# SCH_blinker_2025-11-02.net
KiCad netlist of a schematic drawn in EasyEDA
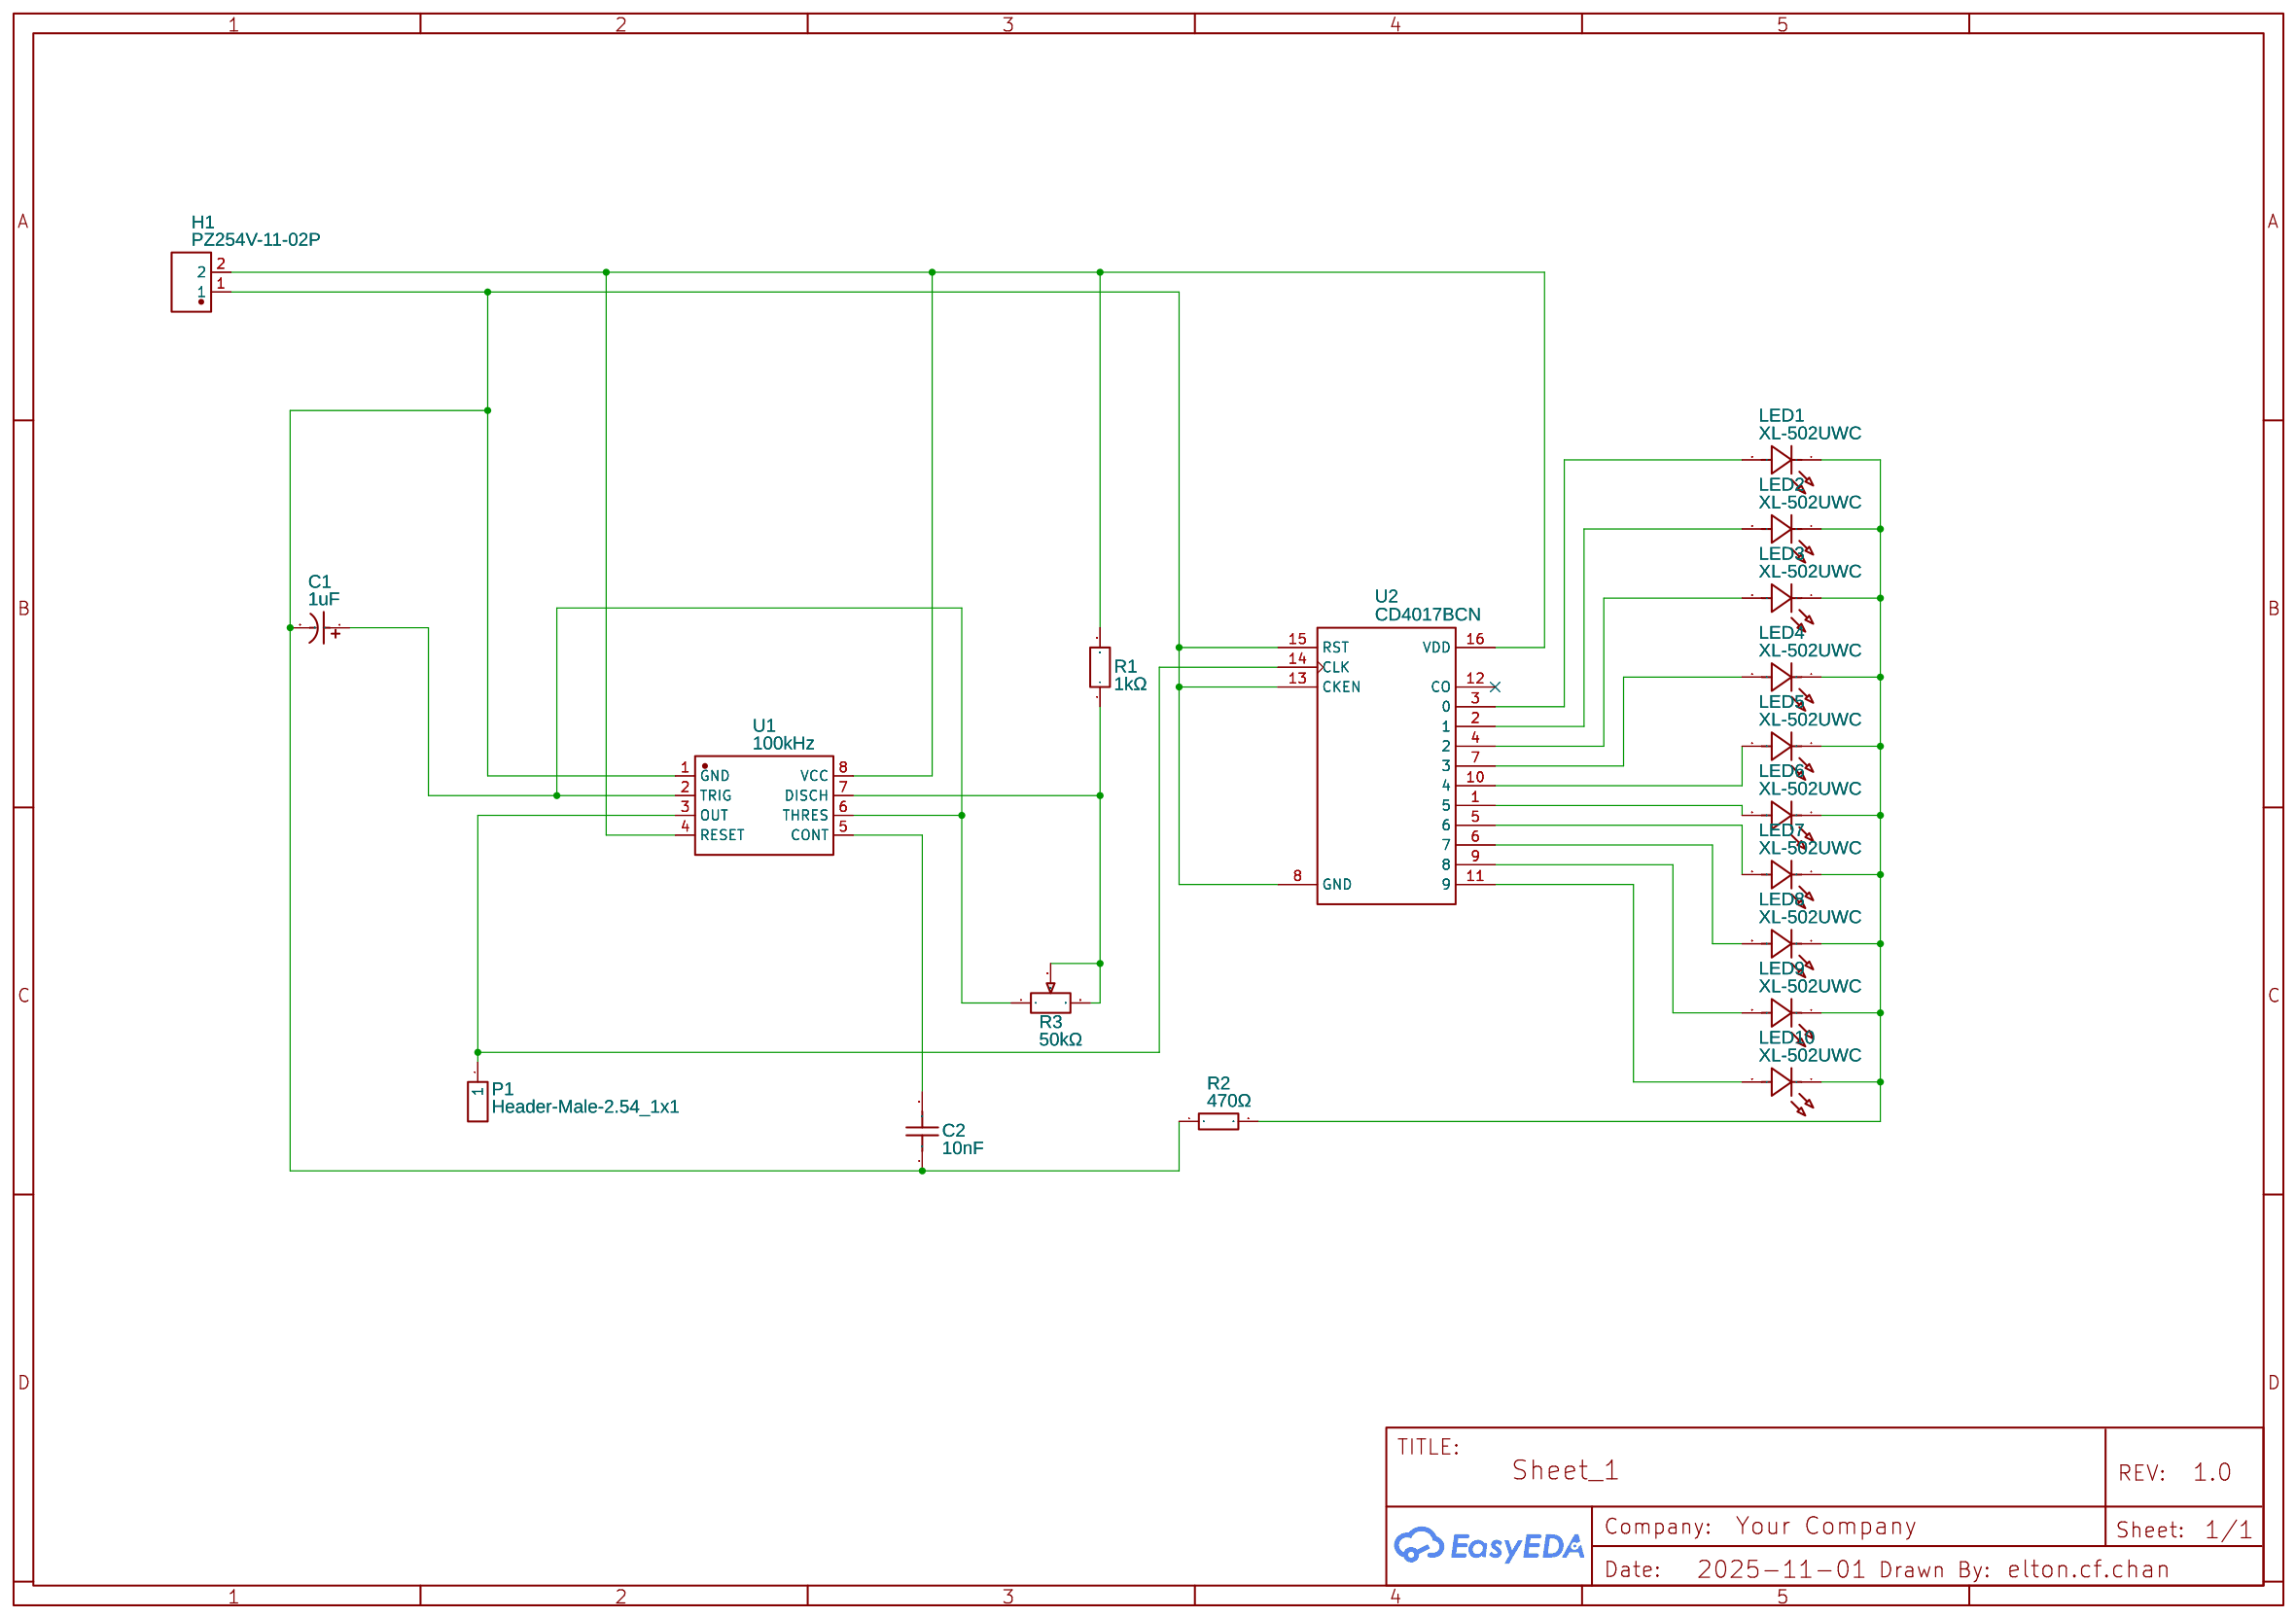
[diagram p0: schematic sheet]

(export (version "E")
  (design (tool "Eeschema 10.0.6"))
  (components
    (comp (ref "C1")
      (value "1uF")
      (fields (field (name "Manufacturer Part") "KF010M050C110A") (field (name "Manufacturer") "CapXon(丰宾)"))
      (libsource (lib "") (part "KF010M050C110A"))
    )
    (comp (ref "C2")
      (value "10nF")
      (fields (field (name "Manufacturer Part") "N09F1B103MN0B0S0N0") (field (name "Manufacturer") "STE(松田)"))
      (libsource (lib "") (part "N09F1B103MN0B0S0N0"))
    )
    (comp (ref "H1")
      (value "PZ254V-11-02P")
      (fields (field (name "Manufacturer") "XFCN(兴飞)"))
      (libsource (lib "") (part "PZ254V-11-02P"))
    )
    (comp (ref "LED1")
      (value "XL-502UWC")
      (fields (field (name "Manufacturer") "XINGLIGHT(成兴光)"))
      (libsource (lib "") (part "XL-502UWC"))
    )
    (comp (ref "LED2")
      (value "XL-502UWC")
      (fields (field (name "Manufacturer") "XINGLIGHT(成兴光)"))
      (libsource (lib "") (part "XL-502UWC"))
    )
    (comp (ref "LED3")
      (value "XL-502UWC")
      (fields (field (name "Manufacturer") "XINGLIGHT(成兴光)"))
      (libsource (lib "") (part "XL-502UWC"))
    )
    (comp (ref "LED4")
      (value "XL-502UWC")
      (fields (field (name "Manufacturer") "XINGLIGHT(成兴光)"))
      (libsource (lib "") (part "XL-502UWC"))
    )
    (comp (ref "LED5")
      (value "XL-502UWC")
      (fields (field (name "Manufacturer") "XINGLIGHT(成兴光)"))
      (libsource (lib "") (part "XL-502UWC"))
    )
    (comp (ref "LED6")
      (value "XL-502UWC")
      (fields (field (name "Manufacturer") "XINGLIGHT(成兴光)"))
      (libsource (lib "") (part "XL-502UWC"))
    )
    (comp (ref "LED7")
      (value "XL-502UWC")
      (fields (field (name "Manufacturer") "XINGLIGHT(成兴光)"))
      (libsource (lib "") (part "XL-502UWC"))
    )
    (comp (ref "LED8")
      (value "XL-502UWC")
      (fields (field (name "Manufacturer") "XINGLIGHT(成兴光)"))
      (libsource (lib "") (part "XL-502UWC"))
    )
    (comp (ref "LED9")
      (value "XL-502UWC")
      (fields (field (name "Manufacturer") "XINGLIGHT(成兴光)"))
      (libsource (lib "") (part "XL-502UWC"))
    )
    (comp (ref "LED10")
      (value "XL-502UWC")
      (fields (field (name "Manufacturer") "XINGLIGHT(成兴光)"))
      (libsource (lib "") (part "XL-502UWC"))
    )
    (comp (ref "P1")
      (value "Header-Male-2.54_1x1")
      (fields (field (name "Manufacturer Part") "2.54-1*1P针") (field (name "Manufacturer") "BOOMELE(博穆精密)"))
      (libsource (lib "") (part "Header-Male-2.54_1x1"))
    )
    (comp (ref "R1")
      (value "1kΩ")
      (fields (field (name "Manufacturer Part") "MF1/4W-1KΩ±1%T52") (field (name "Manufacturer") "华星机电"))
      (libsource (lib "") (part "MF1/4W-1KΩ±1%T52"))
    )
    (comp (ref "R2")
      (value "470Ω")
      (fields
        (field (name "Manufacturer Part") "MFR0W4F4700A50")
        (field (name "Manufacturer") "UNI-ROYAL(厚声)")
      )
      (libsource (lib "") (part "MFR0W4F4700A50"))
    )
    (comp (ref "R3")
      (value "50kΩ")
      (fields (field (name "Manufacturer Part") "3296X-1-503") (field (name "Manufacturer") "BOCHEN(博晨)"))
      (libsource (lib "") (part "3296X-1-503_C118912"))
    )
    (comp (ref "U1")
      (value "100kHz")
      (fields (field (name "Manufacturer Part") "NE555P") (field (name "Manufacturer") "TI(德州仪器)"))
      (libsource (lib "") (part "NE555P"))
    )
    (comp (ref "U2") (value "CD4017BCN") (libsource (lib "") (part "CD4017BCN")))
  )
  (nets
    (net (code "1") (name "Net-(LED1-A)") (class "Default")
      (node (ref "LED1") (pin "2") (pinfunction "A_2") (pintype "unspecified"))
      (node (ref "U2") (pin "3") (pinfunction "0_3") (pintype "output"))
    )
    (net (code "2") (name "Net-(LED1-K)") (class "Default")
      (node (ref "LED1") (pin "1") (pinfunction "K_1") (pintype "unspecified"))
      (node (ref "LED10") (pin "1") (pinfunction "K_1") (pintype "unspecified"))
      (node (ref "LED2") (pin "1") (pinfunction "K_1") (pintype "unspecified"))
      (node (ref "LED3") (pin "1") (pinfunction "K_1") (pintype "unspecified"))
      (node (ref "LED4") (pin "1") (pinfunction "K_1") (pintype "unspecified"))
      (node (ref "LED5") (pin "1") (pinfunction "K_1") (pintype "unspecified"))
      (node (ref "LED6") (pin "1") (pinfunction "K_1") (pintype "unspecified"))
      (node (ref "LED7") (pin "1") (pinfunction "K_1") (pintype "unspecified"))
      (node (ref "LED8") (pin "1") (pinfunction "K_1") (pintype "unspecified"))
      (node (ref "LED9") (pin "1") (pinfunction "K_1") (pintype "unspecified"))
      (node (ref "R2") (pin "2") (pinfunction "2_2") (pintype "input"))
    )
    (net (code "3") (name "Net-(LED2-A)") (class "Default")
      (node (ref "LED2") (pin "2") (pinfunction "A_2") (pintype "unspecified"))
      (node (ref "U2") (pin "2") (pinfunction "1_2") (pintype "output"))
    )
    (net (code "4") (name "Net-(LED3-A)") (class "Default")
      (node (ref "LED3") (pin "2") (pinfunction "A_2") (pintype "unspecified"))
      (node (ref "U2") (pin "4") (pinfunction "2_4") (pintype "output"))
    )
    (net (code "5") (name "Net-(LED4-A)") (class "Default")
      (node (ref "LED4") (pin "2") (pinfunction "A_2") (pintype "unspecified"))
      (node (ref "U2") (pin "7") (pinfunction "3_7") (pintype "output"))
    )
    (net (code "6") (name "Net-(LED5-A)") (class "Default")
      (node (ref "LED5") (pin "2") (pinfunction "A_2") (pintype "unspecified"))
      (node (ref "U2") (pin "10") (pinfunction "4_10") (pintype "output"))
    )
    (net (code "7") (name "Net-(LED6-A)") (class "Default")
      (node (ref "LED6") (pin "2") (pinfunction "A_2") (pintype "unspecified"))
      (node (ref "U2") (pin "1") (pinfunction "5_1") (pintype "output"))
    )
    (net (code "8") (name "Net-(LED7-A)") (class "Default")
      (node (ref "LED7") (pin "2") (pinfunction "A_2") (pintype "unspecified"))
      (node (ref "U2") (pin "5") (pinfunction "6_5") (pintype "output"))
    )
    (net (code "9") (name "Net-(LED8-A)") (class "Default")
      (node (ref "LED8") (pin "2") (pinfunction "A_2") (pintype "unspecified"))
      (node (ref "U2") (pin "6") (pinfunction "7_6") (pintype "output"))
    )
    (net (code "10") (name "Net-(LED9-A)") (class "Default")
      (node (ref "LED9") (pin "2") (pinfunction "A_2") (pintype "unspecified"))
      (node (ref "U2") (pin "9") (pinfunction "8_9") (pintype "output"))
    )
    (net (code "11") (name "Net-(LED10-A)") (class "Default")
      (node (ref "LED10") (pin "2") (pinfunction "A_2") (pintype "unspecified"))
      (node (ref "U2") (pin "11") (pinfunction "9_11") (pintype "output"))
    )
    (net (code "12") (name "Net-(U1-CONT)") (class "Default")
      (node (ref "C2") (pin "2") (pinfunction "2_2") (pintype "unspecified"))
      (node (ref "U1") (pin "5") (pinfunction "CONT_5") (pintype "unspecified"))
    )
    (net (code "13") (name "Net-(U1-DISCH)") (class "Default")
      (node (ref "R1") (pin "1") (pinfunction "1_1") (pintype "unspecified"))
      (node (ref "R3") (pin "2") (pinfunction "2_2") (pintype "input"))
      (node (ref "R3") (pin "3") (pinfunction "3_3") (pintype "input"))
      (node (ref "U1") (pin "7") (pinfunction "DISCH_7") (pintype "unspecified"))
    )
    (net (code "14") (name "Net-(U1-GND)") (class "Default")
      (node (ref "C1") (pin "2") (pinfunction "2_2") (pintype "input"))
      (node (ref "C2") (pin "1") (pinfunction "1_1") (pintype "unspecified"))
      (node (ref "H1") (pin "1") (pinfunction "1_1") (pintype "unspecified"))
      (node (ref "R2") (pin "1") (pinfunction "1_1") (pintype "input"))
      (node (ref "U1") (pin "1") (pinfunction "GND_1") (pintype "unspecified"))
      (node (ref "U2") (pin "13") (pinfunction "CKEN_13") (pintype "unspecified"))
      (node (ref "U2") (pin "15") (pinfunction "RST_15") (pintype "unspecified"))
      (node (ref "U2") (pin "8") (pinfunction "GND_8") (pintype "passive"))
    )
    (net (code "15") (name "Net-(U1-OUT)") (class "Default")
      (node (ref "P1") (pin "1") (pinfunction "1_1") (pintype "input"))
      (node (ref "U1") (pin "3") (pinfunction "OUT_3") (pintype "unspecified"))
      (node (ref "U2") (pin "14") (pinfunction "CLK_14") (pintype "unspecified"))
    )
    (net (code "16") (name "Net-(U1-RESET)") (class "Default")
      (node (ref "H1") (pin "2") (pinfunction "2_2") (pintype "unspecified"))
      (node (ref "R1") (pin "2") (pinfunction "2_2") (pintype "unspecified"))
      (node (ref "U1") (pin "4") (pinfunction "RESET_4") (pintype "unspecified"))
      (node (ref "U1") (pin "8") (pinfunction "VCC_8") (pintype "unspecified"))
      (node (ref "U2") (pin "16") (pinfunction "VDD_16") (pintype "passive"))
    )
    (net (code "17") (name "Net-(U1-THRES)") (class "Default")
      (node (ref "C1") (pin "1") (pinfunction "1_1") (pintype "input"))
      (node (ref "R3") (pin "1") (pinfunction "1_1") (pintype "input"))
      (node (ref "U1") (pin "2") (pinfunction "TRIG_2") (pintype "unspecified"))
      (node (ref "U1") (pin "6") (pinfunction "THRES_6") (pintype "unspecified"))
    )
    (net (code "18") (name "unconnected-(U2-CO-Pad12)") (class "Default")
      (node (ref "U2") (pin "12") (pinfunction "CO_12") (pintype "output+no_connect"))
    )
  )
)
